# NVMe__Networking__Ports.net
KiCad netlist of a schematic drawn in Altium Designer
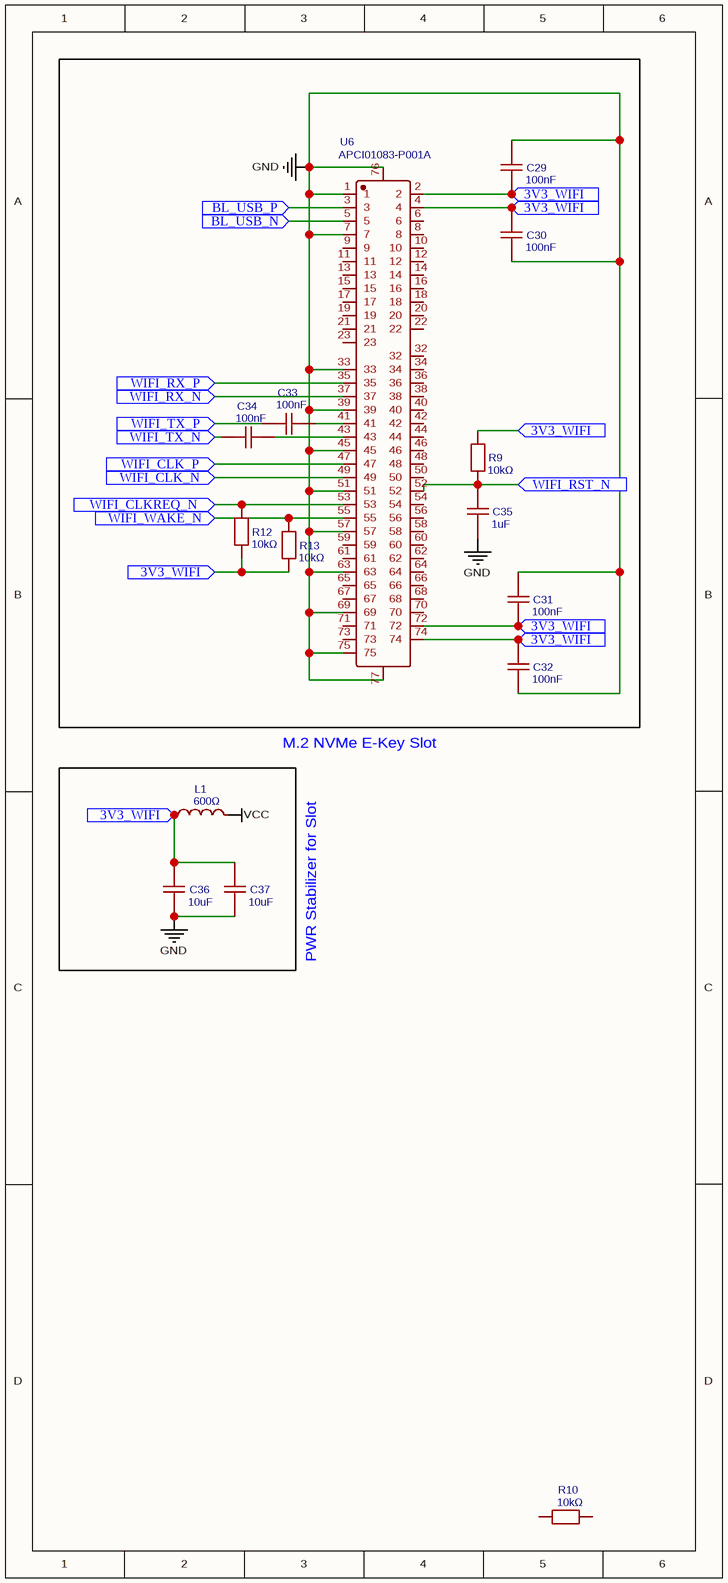
[diagram p0: NVMe_(Networking)_Ports.schdoc]

(export (version "E")
  (design (tool "Eeschema 10.0.6"))
  (components
    (comp (ref "C29")
      (value "100nF")
      (fields
        (field (name "MANUFACTURER") "YAGEO(国巨)")
        (field (name "MANUFACTURER PART") "CC0402KRX5R6BB104")
        (field (name "CONTRIBUTOR") "LCSC")
      )
      (libsource (lib "altium-import") (part "root_1_100nF_"))
    )
    (comp (ref "C30")
      (value "100nF")
      (fields
        (field (name "MANUFACTURER") "YAGEO(国巨)")
        (field (name "MANUFACTURER PART") "CC0402KRX5R6BB104")
        (field (name "CONTRIBUTOR") "LCSC")
      )
      (libsource (lib "altium-import") (part "root_1_100nF_"))
    )
    (comp (ref "C31")
      (value "100nF")
      (fields
        (field (name "MANUFACTURER") "YAGEO(国巨)")
        (field (name "MANUFACTURER PART") "CC0402KRX5R6BB104")
        (field (name "CONTRIBUTOR") "LCSC")
      )
      (libsource (lib "altium-import") (part "root_1_100nF_"))
    )
    (comp (ref "C32")
      (value "100nF")
      (fields
        (field (name "MANUFACTURER") "YAGEO(国巨)")
        (field (name "MANUFACTURER PART") "CC0402KRX5R6BB104")
        (field (name "CONTRIBUTOR") "LCSC")
      )
      (libsource (lib "altium-import") (part "root_1_100nF_"))
    )
    (comp (ref "C33")
      (value "100nF")
      (fields
        (field (name "MANUFACTURER") "YAGEO(国巨)")
        (field (name "MANUFACTURER PART") "CC0402KRX5R6BB104")
        (field (name "CONTRIBUTOR") "LCSC")
      )
      (libsource (lib "altium-import") (part "root_2_100nF_"))
    )
    (comp (ref "C34")
      (value "100nF")
      (fields
        (field (name "MANUFACTURER") "YAGEO(国巨)")
        (field (name "MANUFACTURER PART") "CC0402KRX5R6BB104")
        (field (name "CONTRIBUTOR") "LCSC")
      )
      (libsource (lib "altium-import") (part "root_2_100nF_"))
    )
    (comp (ref "C35")
      (value "1uF")
      (fields
        (field (name "MANUFACTURER") "CCTC(三环)")
        (field (name "MANUFACTURER PART") "TCC0402X5R105K160AT")
        (field (name "CONTRIBUTOR") "lcsc")
      )
      (libsource (lib "altium-import") (part "root_1_1uF_"))
    )
    (comp (ref "C36")
      (value "10uF")
      (fields
        (field (name "MANUFACTURER") "HRE(芯声)")
        (field (name "MANUFACTURER PART") "CGA0805X5R106K500MT")
        (field (name "CONTRIBUTOR") "lcsc")
      )
      (libsource (lib "altium-import") (part "root_1_10uF_"))
    )
    (comp (ref "C37")
      (value "10uF")
      (fields
        (field (name "MANUFACTURER") "HRE(芯声)")
        (field (name "MANUFACTURER PART") "CGA0805X5R106K500MT")
        (field (name "CONTRIBUTOR") "lcsc")
      )
      (libsource (lib "altium-import") (part "root_1_10uF_"))
    )
    (comp (ref "L1")
      (value "600Ω")
      (fields (field (name "MANUFACTURER") "TDK") (field (name "MANUFACTURER PART") "MPZ2012S601AT000"))
      (libsource (lib "altium-import") (part "root_0_600Ω_"))
    )
    (comp (ref "R9")
      (value "10kΩ")
      (fields
        (field (name "MANUFACTURER") "FOJAN(富捷)")
        (field (name "MANUFACTURER PART") "FRC0402F1002TS")
        (field (name "CONTRIBUTOR") "LCSC")
      )
      (libsource (lib "altium-import") (part "root_1_10kΩ_"))
    )
    (comp (ref "R10")
      (value "10kΩ")
      (fields
        (field (name "MANUFACTURER") "FOJAN(富捷)")
        (field (name "MANUFACTURER PART") "FRC0402F1002TS")
        (field (name "CONTRIBUTOR") "LCSC")
      )
      (libsource (lib "altium-import") (part "root_0_10kΩ_"))
    )
    (comp (ref "R12")
      (value "10kΩ")
      (fields
        (field (name "MANUFACTURER") "FOJAN(富捷)")
        (field (name "MANUFACTURER PART") "FRC0402F1002TS")
        (field (name "CONTRIBUTOR") "LCSC")
      )
      (libsource (lib "altium-import") (part "root_1_10kΩ_"))
    )
    (comp (ref "R13")
      (value "10kΩ")
      (fields
        (field (name "MANUFACTURER") "FOJAN(富捷)")
        (field (name "MANUFACTURER PART") "FRC0402F1002TS")
        (field (name "CONTRIBUTOR") "LCSC")
      )
      (libsource (lib "altium-import") (part "root_1_10kΩ_"))
    )
    (comp (ref "U6")
      (value "APCI01083-P001A")
      (fields (field (name "MANUFACTURER") "LX(连欣科技)") (field (name "CONTRIBUTOR") "lcsc"))
      (libsource (lib "altium-import") (part "root_0_APCI01083-P001A_"))
    )
  )
  (nets
    (net (code "1") (name "/3V3_WIFI") (class "Default")
      (node (ref "C29") (pin "1") (pinfunction "1_1") (pintype "passive"))
      (node (ref "C30") (pin "2") (pinfunction "2_2") (pintype "passive"))
      (node (ref "C31") (pin "1") (pinfunction "1_1") (pintype "passive"))
      (node (ref "C32") (pin "2") (pinfunction "2_2") (pintype "passive"))
      (node (ref "C36") (pin "2") (pinfunction "2_2") (pintype "passive"))
      (node (ref "C37") (pin "2") (pinfunction "2_2") (pintype "passive"))
      (node (ref "L1") (pin "1") (pinfunction "1_1") (pintype "passive"))
      (node (ref "R12") (pin "1") (pinfunction "1_1") (pintype "passive"))
      (node (ref "R13") (pin "1") (pinfunction "1_1") (pintype "passive"))
      (node (ref "R9") (pin "2") (pinfunction "2_2") (pintype "passive"))
      (node (ref "U6") (pin "2") (pinfunction "2_2") (pintype "passive"))
      (node (ref "U6") (pin "4") (pinfunction "4_4") (pintype "passive"))
      (node (ref "U6") (pin "72") (pinfunction "72_72") (pintype "passive"))
      (node (ref "U6") (pin "74") (pinfunction "74_74") (pintype "passive"))
    )
    (net (code "2") (name "/BL_USB_N") (class "Default")
      (node (ref "U6") (pin "5") (pinfunction "5_5") (pintype "passive"))
    )
    (net (code "3") (name "/BL_USB_P") (class "Default")
      (node (ref "U6") (pin "3") (pinfunction "3_3") (pintype "passive"))
    )
    (net (code "4") (name "/WIFI_CLKREQ_N") (class "Default")
      (node (ref "R12") (pin "2") (pinfunction "2_2") (pintype "passive"))
      (node (ref "U6") (pin "53") (pinfunction "53_53") (pintype "passive"))
    )
    (net (code "5") (name "/WIFI_CLK_N") (class "Default")
      (node (ref "U6") (pin "49") (pinfunction "49_49") (pintype "passive"))
    )
    (net (code "6") (name "/WIFI_CLK_P") (class "Default")
      (node (ref "U6") (pin "47") (pinfunction "47_47") (pintype "passive"))
    )
    (net (code "7") (name "/WIFI_RST_N") (class "Default")
      (node (ref "C35") (pin "2") (pinfunction "2_2") (pintype "passive"))
      (node (ref "R9") (pin "1") (pinfunction "1_1") (pintype "passive"))
      (node (ref "U6") (pin "52") (pinfunction "52_52") (pintype "passive"))
    )
    (net (code "8") (name "/WIFI_RX_N") (class "Default")
      (node (ref "U6") (pin "37") (pinfunction "37_37") (pintype "passive"))
    )
    (net (code "9") (name "/WIFI_RX_P") (class "Default")
      (node (ref "U6") (pin "35") (pinfunction "35_35") (pintype "passive"))
    )
    (net (code "10") (name "/WIFI_TX_N") (class "Default")
      (node (ref "C34") (pin "2") (pinfunction "2_2") (pintype "passive"))
    )
    (net (code "11") (name "/WIFI_TX_P") (class "Default")
      (node (ref "C33") (pin "2") (pinfunction "2_2") (pintype "passive"))
    )
    (net (code "12") (name "/WIFI_WAKE_N") (class "Default")
      (node (ref "R13") (pin "2") (pinfunction "2_2") (pintype "passive"))
      (node (ref "U6") (pin "55") (pinfunction "55_55") (pintype "passive"))
    )
    (net (code "13") (name "GND") (class "Default")
      (node (ref "C29") (pin "2") (pinfunction "2_2") (pintype "passive"))
      (node (ref "C30") (pin "1") (pinfunction "1_1") (pintype "passive"))
      (node (ref "C31") (pin "2") (pinfunction "2_2") (pintype "passive"))
      (node (ref "C32") (pin "1") (pinfunction "1_1") (pintype "passive"))
      (node (ref "C35") (pin "1") (pinfunction "1_1") (pintype "passive"))
      (node (ref "C36") (pin "1") (pinfunction "1_1") (pintype "passive"))
      (node (ref "C37") (pin "1") (pinfunction "1_1") (pintype "passive"))
      (node (ref "U6") (pin "1") (pinfunction "1_1") (pintype "passive"))
      (node (ref "U6") (pin "33") (pinfunction "33_33") (pintype "passive"))
      (node (ref "U6") (pin "39") (pinfunction "39_39") (pintype "passive"))
      (node (ref "U6") (pin "45") (pinfunction "45_45") (pintype "passive"))
      (node (ref "U6") (pin "51") (pinfunction "51_51") (pintype "passive"))
      (node (ref "U6") (pin "57") (pinfunction "57_57") (pintype "passive"))
      (node (ref "U6") (pin "63") (pinfunction "63_63") (pintype "passive"))
      (node (ref "U6") (pin "69") (pinfunction "69_69") (pintype "passive"))
      (node (ref "U6") (pin "7") (pinfunction "7_7") (pintype "passive"))
      (node (ref "U6") (pin "75") (pinfunction "75_75") (pintype "passive"))
      (node (ref "U6") (pin "76") (pinfunction "76_76") (pintype "passive"))
      (node (ref "U6") (pin "77") (pinfunction "77_77") (pintype "passive"))
    )
    (net (code "14") (name "Net-(C33-Pad1)") (class "Default")
      (node (ref "C33") (pin "1") (pinfunction "1_1") (pintype "passive"))
      (node (ref "U6") (pin "41") (pinfunction "41_41") (pintype "passive"))
    )
    (net (code "15") (name "Net-(C34-Pad1)") (class "Default")
      (node (ref "C34") (pin "1") (pinfunction "1_1") (pintype "passive"))
      (node (ref "U6") (pin "43") (pinfunction "43_43") (pintype "passive"))
    )
    (net (code "16") (name "VCC") (class "Default")
      (node (ref "L1") (pin "2") (pinfunction "2_2") (pintype "passive"))
    )
    (net (code "17") (name "unconnected-(R10-Pad1)") (class "Default")
      (node (ref "R10") (pin "1") (pinfunction "1_1") (pintype "passive"))
    )
    (net (code "18") (name "unconnected-(R10-Pad2)") (class "Default")
      (node (ref "R10") (pin "2") (pinfunction "2_2") (pintype "passive"))
    )
    (net (code "19") (name "unconnected-(U6-Pad6)") (class "Default")
      (node (ref "U6") (pin "6") (pinfunction "6_6") (pintype "passive"))
    )
    (net (code "20") (name "unconnected-(U6-Pad8)") (class "Default")
      (node (ref "U6") (pin "8") (pinfunction "8_8") (pintype "passive"))
    )
    (net (code "21") (name "unconnected-(U6-Pad9)") (class "Default")
      (node (ref "U6") (pin "9") (pinfunction "9_9") (pintype "passive"))
    )
    (net (code "22") (name "unconnected-(U6-Pad10)") (class "Default")
      (node (ref "U6") (pin "10") (pinfunction "10_10") (pintype "passive"))
    )
    (net (code "23") (name "unconnected-(U6-Pad11)") (class "Default")
      (node (ref "U6") (pin "11") (pinfunction "11_11") (pintype "passive"))
    )
    (net (code "24") (name "unconnected-(U6-Pad12)") (class "Default")
      (node (ref "U6") (pin "12") (pinfunction "12_12") (pintype "passive"))
    )
    (net (code "25") (name "unconnected-(U6-Pad13)") (class "Default")
      (node (ref "U6") (pin "13") (pinfunction "13_13") (pintype "passive"))
    )
    (net (code "26") (name "unconnected-(U6-Pad14)") (class "Default")
      (node (ref "U6") (pin "14") (pinfunction "14_14") (pintype "passive"))
    )
    (net (code "27") (name "unconnected-(U6-Pad15)") (class "Default")
      (node (ref "U6") (pin "15") (pinfunction "15_15") (pintype "passive"))
    )
    (net (code "28") (name "unconnected-(U6-Pad16)") (class "Default")
      (node (ref "U6") (pin "16") (pinfunction "16_16") (pintype "passive"))
    )
    (net (code "29") (name "unconnected-(U6-Pad17)") (class "Default")
      (node (ref "U6") (pin "17") (pinfunction "17_17") (pintype "passive"))
    )
    (net (code "30") (name "unconnected-(U6-Pad18)") (class "Default")
      (node (ref "U6") (pin "18") (pinfunction "18_18") (pintype "passive"))
    )
    (net (code "31") (name "unconnected-(U6-Pad19)") (class "Default")
      (node (ref "U6") (pin "19") (pinfunction "19_19") (pintype "passive"))
    )
    (net (code "32") (name "unconnected-(U6-Pad20)") (class "Default")
      (node (ref "U6") (pin "20") (pinfunction "20_20") (pintype "passive"))
    )
    (net (code "33") (name "unconnected-(U6-Pad21)") (class "Default")
      (node (ref "U6") (pin "21") (pinfunction "21_21") (pintype "passive"))
    )
    (net (code "34") (name "unconnected-(U6-Pad22)") (class "Default")
      (node (ref "U6") (pin "22") (pinfunction "22_22") (pintype "passive"))
    )
    (net (code "35") (name "unconnected-(U6-Pad23)") (class "Default")
      (node (ref "U6") (pin "23") (pinfunction "23_23") (pintype "passive"))
    )
    (net (code "36") (name "unconnected-(U6-Pad32)") (class "Default")
      (node (ref "U6") (pin "32") (pinfunction "32_32") (pintype "passive"))
    )
    (net (code "37") (name "unconnected-(U6-Pad34)") (class "Default")
      (node (ref "U6") (pin "34") (pinfunction "34_34") (pintype "passive"))
    )
    (net (code "38") (name "unconnected-(U6-Pad36)") (class "Default")
      (node (ref "U6") (pin "36") (pinfunction "36_36") (pintype "passive"))
    )
    (net (code "39") (name "unconnected-(U6-Pad38)") (class "Default")
      (node (ref "U6") (pin "38") (pinfunction "38_38") (pintype "passive"))
    )
    (net (code "40") (name "unconnected-(U6-Pad40)") (class "Default")
      (node (ref "U6") (pin "40") (pinfunction "40_40") (pintype "passive"))
    )
    (net (code "41") (name "unconnected-(U6-Pad42)") (class "Default")
      (node (ref "U6") (pin "42") (pinfunction "42_42") (pintype "passive"))
    )
    (net (code "42") (name "unconnected-(U6-Pad44)") (class "Default")
      (node (ref "U6") (pin "44") (pinfunction "44_44") (pintype "passive"))
    )
    (net (code "43") (name "unconnected-(U6-Pad46)") (class "Default")
      (node (ref "U6") (pin "46") (pinfunction "46_46") (pintype "passive"))
    )
    (net (code "44") (name "unconnected-(U6-Pad48)") (class "Default")
      (node (ref "U6") (pin "48") (pinfunction "48_48") (pintype "passive"))
    )
    (net (code "45") (name "unconnected-(U6-Pad50)") (class "Default")
      (node (ref "U6") (pin "50") (pinfunction "50_50") (pintype "passive"))
    )
    (net (code "46") (name "unconnected-(U6-Pad54)") (class "Default")
      (node (ref "U6") (pin "54") (pinfunction "54_54") (pintype "passive"))
    )
    (net (code "47") (name "unconnected-(U6-Pad56)") (class "Default")
      (node (ref "U6") (pin "56") (pinfunction "56_56") (pintype "passive"))
    )
    (net (code "48") (name "unconnected-(U6-Pad58)") (class "Default")
      (node (ref "U6") (pin "58") (pinfunction "58_58") (pintype "passive"))
    )
    (net (code "49") (name "unconnected-(U6-Pad59)") (class "Default")
      (node (ref "U6") (pin "59") (pinfunction "59_59") (pintype "passive"))
    )
    (net (code "50") (name "unconnected-(U6-Pad60)") (class "Default")
      (node (ref "U6") (pin "60") (pinfunction "60_60") (pintype "passive"))
    )
    (net (code "51") (name "unconnected-(U6-Pad61)") (class "Default")
      (node (ref "U6") (pin "61") (pinfunction "61_61") (pintype "passive"))
    )
    (net (code "52") (name "unconnected-(U6-Pad62)") (class "Default")
      (node (ref "U6") (pin "62") (pinfunction "62_62") (pintype "passive"))
    )
    (net (code "53") (name "unconnected-(U6-Pad64)") (class "Default")
      (node (ref "U6") (pin "64") (pinfunction "64_64") (pintype "passive"))
    )
    (net (code "54") (name "unconnected-(U6-Pad65)") (class "Default")
      (node (ref "U6") (pin "65") (pinfunction "65_65") (pintype "passive"))
    )
    (net (code "55") (name "unconnected-(U6-Pad66)") (class "Default")
      (node (ref "U6") (pin "66") (pinfunction "66_66") (pintype "passive"))
    )
    (net (code "56") (name "unconnected-(U6-Pad67)") (class "Default")
      (node (ref "U6") (pin "67") (pinfunction "67_67") (pintype "passive"))
    )
    (net (code "57") (name "unconnected-(U6-Pad68)") (class "Default")
      (node (ref "U6") (pin "68") (pinfunction "68_68") (pintype "passive"))
    )
    (net (code "58") (name "unconnected-(U6-Pad70)") (class "Default")
      (node (ref "U6") (pin "70") (pinfunction "70_70") (pintype "passive"))
    )
    (net (code "59") (name "unconnected-(U6-Pad71)") (class "Default")
      (node (ref "U6") (pin "71") (pinfunction "71_71") (pintype "passive"))
    )
    (net (code "60") (name "unconnected-(U6-Pad73)") (class "Default")
      (node (ref "U6") (pin "73") (pinfunction "73_73") (pintype "passive"))
    )
  )
)
